# USB_OTG_FS.net
KiCad netlist of a schematic drawn in Altium Designer
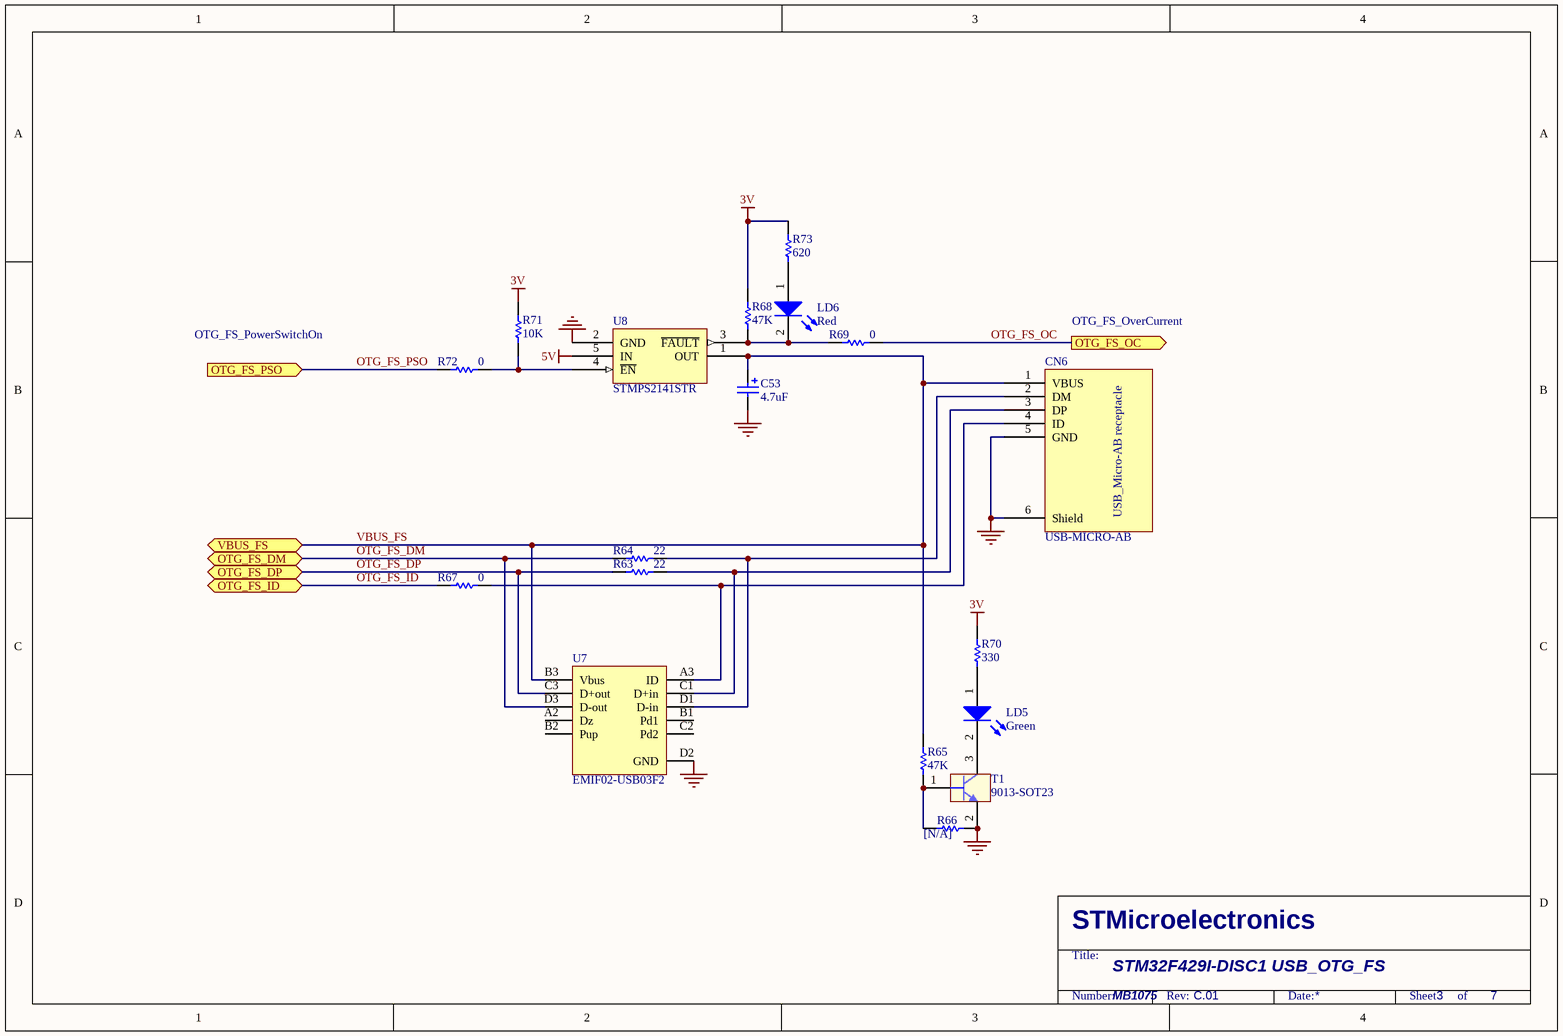
[diagram p0: USB_OTG_FS.SchDoc]

(export (version "E")
  (design (tool "Eeschema 10.0.6"))
  (components
    (comp (ref "C53")
      (value "4.7uF")
      (footprint "TAN-A")
      (description "Polarized Capacitor (Radial)")
      (fields (field (name "PUBLISHER") "Altium Limited"))
      (libsource (lib "Miscellaneous Devices") (part "Cap Pol1"))
    )
    (comp (ref "CN6")
      (value "USB-MICRO-AB")
      (footprint "STM-SMEE:USB-MICRO-AB")
      (description "USB-MICRO-AB, 47590-0001, SMT, MOLEX")
      (libsource (lib "MCD_TOOLS") (part "USB-MICRO-AB"))
    )
    (comp (ref "LD5")
      (value "Green")
      (footprint "0603D")
      (description "Typical RED, GREEN, YELLOW, AMBER GaAs LED")
      (fields (field (name "PUBLISHER") "Altium Limited"))
      (libsource (lib "Miscellaneous Devices") (part "LED2"))
    )
    (comp (ref "LD6")
      (value "Red")
      (footprint "0603D")
      (description "Typical RED, GREEN, YELLOW, AMBER GaAs LED")
      (fields (field (name "PUBLISHER") "Altium Limited"))
      (libsource (lib "Miscellaneous Devices") (part "LED2"))
    )
    (comp (ref "R63")
      (value "22")
      (footprint "0402R")
      (description "Resistor 0402 or 0603 or 0805")
      (libsource (lib "MCD_TOOLS") (part "Resistor_ST"))
    )
    (comp (ref "R64")
      (value "22")
      (footprint "0402R")
      (description "Resistor 0402 or 0603 or 0805")
      (libsource (lib "MCD_TOOLS") (part "Resistor_ST"))
    )
    (comp (ref "R65")
      (value "47K")
      (footprint "0402R")
      (description "Resistor 0402 or 0603 or 0805")
      (libsource (lib "MCD_TOOLS") (part "Resistor_ST"))
    )
    (comp (ref "R66")
      (value "[N/A]")
      (footprint "0402R")
      (description "Resistor 0402 or 0603 or 0805")
      (libsource (lib "MCD_TOOLS") (part "Resistor_ST"))
    )
    (comp (ref "R67")
      (value "0")
      (footprint "0402R")
      (description "Resistor 0402 or 0603 or 0805")
      (libsource (lib "MCD_TOOLS") (part "Resistor_ST"))
    )
    (comp (ref "R68")
      (value "47K")
      (footprint "0402R")
      (description "Resistor 0402 or 0603 or 0805")
      (libsource (lib "MCD_TOOLS") (part "Resistor_ST"))
    )
    (comp (ref "R69")
      (value "0")
      (footprint "0402R")
      (description "Resistor 0402 or 0603 or 0805")
      (libsource (lib "MCD_TOOLS") (part "Resistor_ST"))
    )
    (comp (ref "R70")
      (value "330")
      (footprint "0603R")
      (description "Resistor 0402 or 0603 or 0805")
      (libsource (lib "MCD_TOOLS") (part "Resistor_ST"))
    )
    (comp (ref "R71")
      (value "10K")
      (footprint "0402R")
      (description "Resistor 0402 or 0603 or 0805")
      (libsource (lib "MCD_TOOLS") (part "Resistor_ST"))
    )
    (comp (ref "R72")
      (value "0")
      (footprint "0402R")
      (description "Resistor 0402 or 0603 or 0805")
      (libsource (lib "MCD_TOOLS") (part "Resistor_ST"))
    )
    (comp (ref "R73")
      (value "620")
      (footprint "0603R")
      (description "Resistor 0402 or 0603 or 0805")
      (libsource (lib "MCD_TOOLS") (part "Resistor_ST"))
    )
    (comp (ref "T1")
      (value "9013-SOT23")
      (footprint "SOT-23")
      (description "NPN Bipolar Transistor, SOT-23 Footprint")
      (libsource (lib "MCD_TOOLS") (part "9013-SOT23"))
    )
    (comp (ref "U7")
      (value "EMIF02-USB03F2")
      (footprint "STM-SMEE:Flip Chip")
      (description "2-line IPAD, EMI filter including ESD protection")
      (libsource (lib "MCD_TOOLS") (part "EMIF02-USB03F2"))
    )
    (comp (ref "U8")
      (value "STMPS2141STR")
      (footprint "SOT23-5L")
      (description "Enhanced single channel power switches")
      (libsource (lib "MCD_TOOLS") (part "STMPS2141STR"))
    )
  )
  (nets
    (net (code "1") (name "/OTG_FS_DM") (class "Default")
      (node (ref "R64") (pin "1") (pinfunction "1_1") (pintype "passive"))
      (node (ref "U7") (pin "D3") (pinfunction "D-out_D3") (pintype "passive"))
    )
    (net (code "2") (name "/OTG_FS_DP") (class "Default")
      (node (ref "R63") (pin "1") (pinfunction "1_1") (pintype "passive"))
      (node (ref "U7") (pin "C3") (pinfunction "D+out_C3") (pintype "passive"))
    )
    (net (code "3") (name "/OTG_FS_ID") (class "Default")
      (node (ref "R67") (pin "1") (pinfunction "1_1") (pintype "passive"))
    )
    (net (code "4") (name "/OTG_FS_OC") (class "Default")
      (node (ref "R69") (pin "2") (pinfunction "2_2") (pintype "passive"))
    )
    (net (code "5") (name "/OTG_FS_PSO") (class "Default")
      (node (ref "R72") (pin "1") (pinfunction "1_1") (pintype "passive"))
    )
    (net (code "6") (name "/VBUS_FS") (class "Default")
      (node (ref "C53") (pin "1") (pinfunction "1_1") (pintype "passive"))
      (node (ref "CN6") (pin "1") (pinfunction "VBUS_1") (pintype "passive"))
      (node (ref "R65") (pin "2") (pinfunction "2_2") (pintype "passive"))
      (node (ref "U7") (pin "B3") (pinfunction "Vbus_B3") (pintype "passive"))
      (node (ref "U8") (pin "1") (pinfunction "OUT_1") (pintype "passive"))
    )
    (net (code "7") (name "3V") (class "Default")
      (node (ref "R68") (pin "2") (pinfunction "2_2") (pintype "passive"))
      (node (ref "R70") (pin "2") (pinfunction "2_2") (pintype "passive"))
      (node (ref "R71") (pin "2") (pinfunction "2_2") (pintype "passive"))
      (node (ref "R73") (pin "2") (pinfunction "2_2") (pintype "passive"))
    )
    (net (code "8") (name "5V") (class "Default")
      (node (ref "U8") (pin "5") (pinfunction "IN_5") (pintype "passive"))
    )
    (net (code "9") (name "GND") (class "Default")
      (node (ref "C53") (pin "2") (pinfunction "2_2") (pintype "passive"))
      (node (ref "CN6") (pin "5") (pinfunction "GND_5") (pintype "passive"))
      (node (ref "CN6") (pin "6") (pinfunction "Shield_6") (pintype "passive"))
      (node (ref "R66") (pin "2") (pinfunction "2_2") (pintype "passive"))
      (node (ref "T1") (pin "2") (pinfunction "E_2") (pintype "passive"))
      (node (ref "U7") (pin "D2") (pinfunction "GND_D2") (pintype "passive"))
      (node (ref "U8") (pin "2") (pinfunction "GND_2") (pintype "passive"))
    )
    (net (code "10") (name "Net-(CN6-DM)") (class "Default")
      (node (ref "CN6") (pin "2") (pinfunction "DM_2") (pintype "passive"))
      (node (ref "R64") (pin "2") (pinfunction "2_2") (pintype "passive"))
      (node (ref "U7") (pin "D1") (pinfunction "D-in_D1") (pintype "passive"))
    )
    (net (code "11") (name "Net-(CN6-DP)") (class "Default")
      (node (ref "CN6") (pin "3") (pinfunction "DP_3") (pintype "passive"))
      (node (ref "R63") (pin "2") (pinfunction "2_2") (pintype "passive"))
      (node (ref "U7") (pin "C1") (pinfunction "D+in_C1") (pintype "passive"))
    )
    (net (code "12") (name "Net-(CN6-ID)") (class "Default")
      (node (ref "CN6") (pin "4") (pinfunction "ID_4") (pintype "passive"))
      (node (ref "R67") (pin "2") (pinfunction "2_2") (pintype "passive"))
      (node (ref "U7") (pin "A3") (pinfunction "ID_A3") (pintype "passive"))
    )
    (net (code "13") (name "Net-(LD5-A)") (class "Default")
      (node (ref "LD5") (pin "1") (pinfunction "A_1") (pintype "passive"))
      (node (ref "R70") (pin "1") (pinfunction "1_1") (pintype "passive"))
    )
    (net (code "14") (name "Net-(LD5-K)") (class "Default")
      (node (ref "LD5") (pin "2") (pinfunction "K_2") (pintype "passive"))
      (node (ref "T1") (pin "3") (pinfunction "C_3") (pintype "passive"))
    )
    (net (code "15") (name "Net-(LD6-A)") (class "Default")
      (node (ref "LD6") (pin "1") (pinfunction "A_1") (pintype "passive"))
      (node (ref "R73") (pin "1") (pinfunction "1_1") (pintype "passive"))
    )
    (net (code "16") (name "Net-(LD6-K)") (class "Default")
      (node (ref "LD6") (pin "2") (pinfunction "K_2") (pintype "passive"))
      (node (ref "R68") (pin "1") (pinfunction "1_1") (pintype "passive"))
      (node (ref "R69") (pin "1") (pinfunction "1_1") (pintype "passive"))
      (node (ref "U8") (pin "3") (pinfunction "~{FAULT}_3") (pintype "output"))
    )
    (net (code "17") (name "Net-(T1-B)") (class "Default")
      (node (ref "R65") (pin "1") (pinfunction "1_1") (pintype "passive"))
      (node (ref "R66") (pin "1") (pinfunction "1_1") (pintype "passive"))
      (node (ref "T1") (pin "1") (pinfunction "B_1") (pintype "passive"))
    )
    (net (code "18") (name "Net-(U8-~{EN})") (class "Default")
      (node (ref "R71") (pin "1") (pinfunction "1_1") (pintype "passive"))
      (node (ref "R72") (pin "2") (pinfunction "2_2") (pintype "passive"))
      (node (ref "U8") (pin "4") (pinfunction "~{EN}_4") (pintype "input"))
    )
    (net (code "19") (name "unconnected-(U7-Dz-PadA2)") (class "Default")
      (node (ref "U7") (pin "A2") (pinfunction "Dz_A2") (pintype "passive"))
    )
    (net (code "20") (name "unconnected-(U7-Pd1-PadB1)") (class "Default")
      (node (ref "U7") (pin "B1") (pinfunction "Pd1_B1") (pintype "passive"))
    )
    (net (code "21") (name "unconnected-(U7-Pd2-PadC2)") (class "Default")
      (node (ref "U7") (pin "C2") (pinfunction "Pd2_C2") (pintype "passive"))
    )
    (net (code "22") (name "unconnected-(U7-Pup-PadB2)") (class "Default")
      (node (ref "U7") (pin "B2") (pinfunction "Pup_B2") (pintype "passive"))
    )
  )
)
